# hmc830_basic.net
KiCad netlist of a schematic drawn in Altium Designer
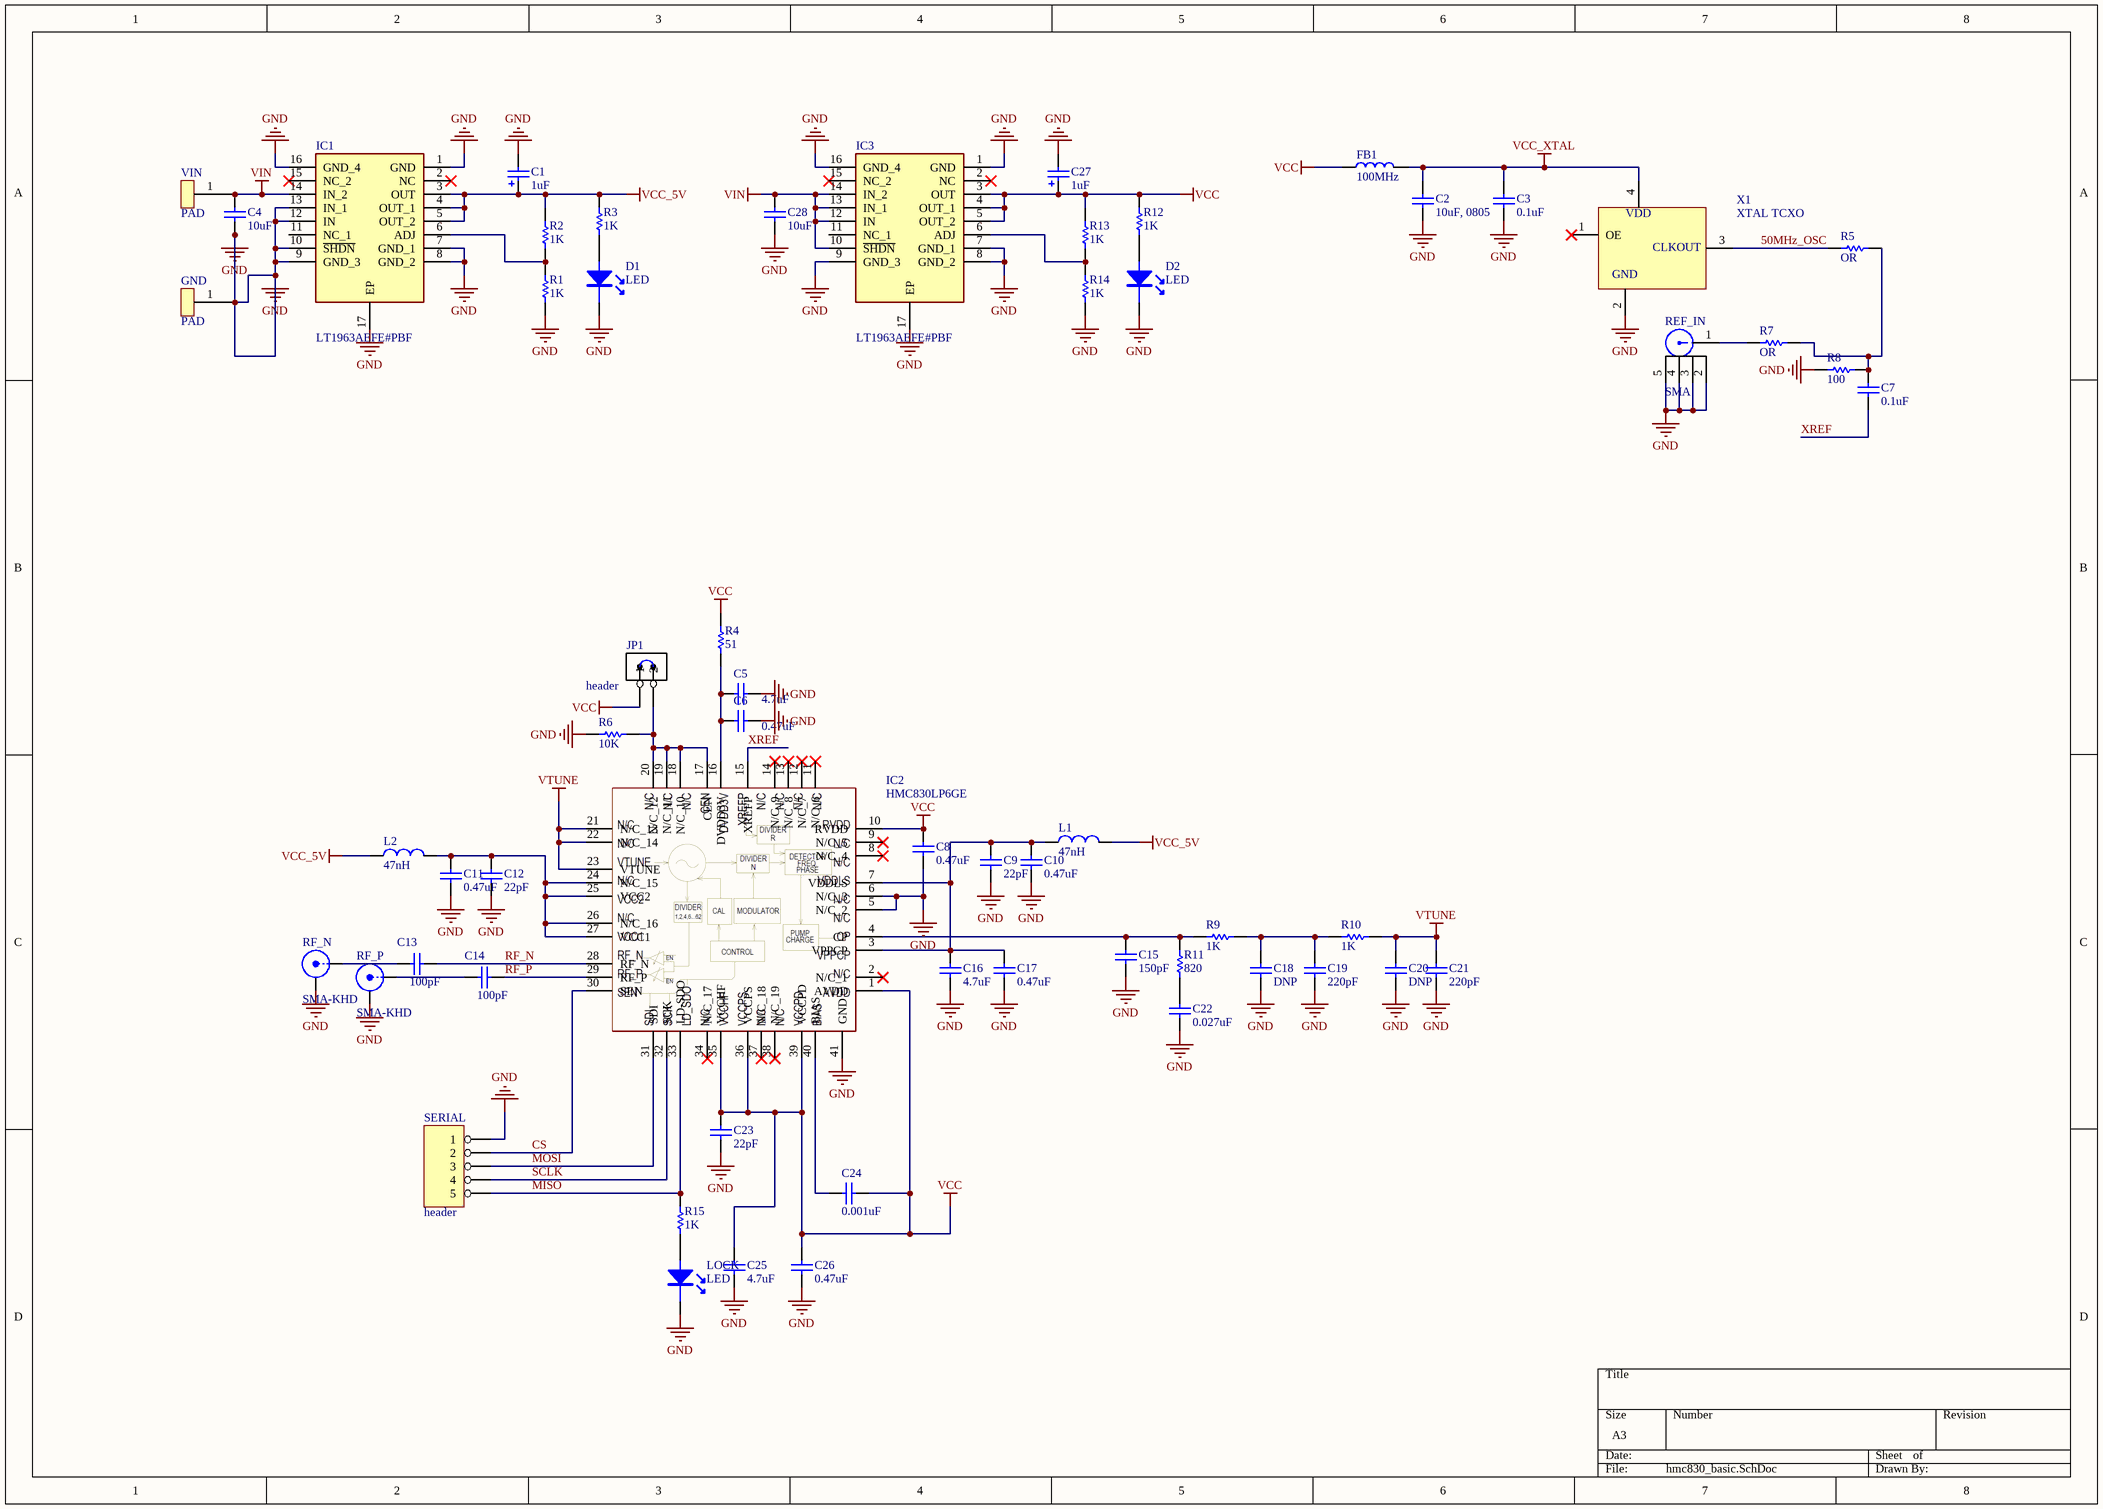
[diagram p0: hmc830_basic.SchDoc]

(export (version "E")
  (design (tool "Eeschema 10.0.6"))
  (components
    (comp (ref "C1")
      (value "1uF")
      (footprint "CAPC3528B")
      (description "Capacitor")
      (fields (field (name "PUBLISHER") "Altium Limited"))
      (libsource (lib "My Footprint") (part "CAP_tan"))
    )
    (comp (ref "C2")
      (value "10uF, 0805")
      (footprint "0805_c")
      (description "Capacitor")
      (fields (field (name "PUBLISHER") "Altium Limited"))
      (libsource (lib "My Footprint") (part "CAP"))
    )
    (comp (ref "C3")
      (value "0.1uF")
      (footprint "0603_C")
      (description "Capacitor")
      (fields (field (name "PUBLISHER") "Altium Limited"))
      (libsource (lib "My Footprint") (part "CAP"))
    )
    (comp (ref "C4")
      (value "10uF")
      (footprint "0805_c")
      (description "Capacitor")
      (fields (field (name "PUBLISHER") "Altium Limited"))
      (libsource (lib "My Footprint") (part "CAP"))
    )
    (comp (ref "C5")
      (value "4.7uF")
      (footprint "0603_C")
      (description "Capacitor")
      (fields (field (name "PUBLISHER") "Altium Limited"))
      (libsource (lib "My Footprint") (part "CAP"))
    )
    (comp (ref "C6")
      (value "0.47uF")
      (footprint "0603_C")
      (description "Capacitor")
      (fields (field (name "PUBLISHER") "Altium Limited"))
      (libsource (lib "My Footprint") (part "CAP"))
    )
    (comp (ref "C7")
      (value "0.1uF")
      (footprint "0603_C")
      (description "Capacitor")
      (fields (field (name "PUBLISHER") "Altium Limited"))
      (libsource (lib "My Footprint") (part "CAP"))
    )
    (comp (ref "C8")
      (value "0.47uF")
      (footprint "0603_C")
      (description "Capacitor")
      (fields (field (name "PUBLISHER") "Altium Limited"))
      (libsource (lib "My Footprint") (part "CAP"))
    )
    (comp (ref "C9")
      (value "22pF")
      (footprint "0603_C")
      (description "Capacitor")
      (fields (field (name "PUBLISHER") "Altium Limited"))
      (libsource (lib "My Footprint") (part "CAP"))
    )
    (comp (ref "C10")
      (value "0.47uF")
      (footprint "0603_C")
      (description "Capacitor")
      (fields (field (name "PUBLISHER") "Altium Limited"))
      (libsource (lib "My Footprint") (part "CAP"))
    )
    (comp (ref "C11")
      (value "0.47uF")
      (footprint "0603_C")
      (description "Capacitor")
      (fields (field (name "PUBLISHER") "Altium Limited"))
      (libsource (lib "My Footprint") (part "CAP"))
    )
    (comp (ref "C12")
      (value "22pF")
      (footprint "0603_C")
      (description "Capacitor")
      (fields (field (name "PUBLISHER") "Altium Limited"))
      (libsource (lib "My Footprint") (part "CAP"))
    )
    (comp (ref "C13")
      (value "100pF")
      (footprint "0603_C")
      (description "Capacitor")
      (fields (field (name "PUBLISHER") "Altium Limited"))
      (libsource (lib "My Footprint") (part "CAP"))
    )
    (comp (ref "C14")
      (value "100pF")
      (footprint "0603_C")
      (description "Capacitor")
      (fields (field (name "PUBLISHER") "Altium Limited"))
      (libsource (lib "My Footprint") (part "CAP"))
    )
    (comp (ref "C15")
      (value "150pF")
      (footprint "0603_C")
      (description "Capacitor")
      (fields (field (name "PUBLISHER") "Altium Limited"))
      (libsource (lib "My Footprint") (part "CAP"))
    )
    (comp (ref "C16")
      (value "4.7uF")
      (footprint "0603_C")
      (description "Capacitor")
      (fields (field (name "PUBLISHER") "Altium Limited"))
      (libsource (lib "My Footprint") (part "CAP"))
    )
    (comp (ref "C17")
      (value "0.47uF")
      (footprint "0603_C")
      (description "Capacitor")
      (fields (field (name "PUBLISHER") "Altium Limited"))
      (libsource (lib "My Footprint") (part "CAP"))
    )
    (comp (ref "C18")
      (value "DNP")
      (footprint "0603_C")
      (description "Capacitor")
      (fields (field (name "PUBLISHER") "Altium Limited"))
      (libsource (lib "My Footprint") (part "CAP"))
    )
    (comp (ref "C19")
      (value "220pF")
      (footprint "0603_C")
      (description "Capacitor")
      (fields (field (name "PUBLISHER") "Altium Limited"))
      (libsource (lib "My Footprint") (part "CAP"))
    )
    (comp (ref "C20")
      (value "DNP")
      (footprint "0603_C")
      (description "Capacitor")
      (fields (field (name "PUBLISHER") "Altium Limited"))
      (libsource (lib "My Footprint") (part "CAP"))
    )
    (comp (ref "C21")
      (value "220pF")
      (footprint "0603_C")
      (description "Capacitor")
      (fields (field (name "PUBLISHER") "Altium Limited"))
      (libsource (lib "My Footprint") (part "CAP"))
    )
    (comp (ref "C22")
      (value "0.027uF")
      (footprint "0603_C")
      (description "Capacitor")
      (fields (field (name "PUBLISHER") "Altium Limited"))
      (libsource (lib "My Footprint") (part "CAP"))
    )
    (comp (ref "C23")
      (value "22pF")
      (footprint "0603_C")
      (description "Capacitor")
      (fields (field (name "PUBLISHER") "Altium Limited"))
      (libsource (lib "My Footprint") (part "CAP"))
    )
    (comp (ref "C24")
      (value "0.001uF")
      (footprint "0603_C")
      (description "Capacitor")
      (fields (field (name "PUBLISHER") "Altium Limited"))
      (libsource (lib "My Footprint") (part "CAP"))
    )
    (comp (ref "C25")
      (value "4.7uF")
      (footprint "0603_C")
      (description "Capacitor")
      (fields (field (name "PUBLISHER") "Altium Limited"))
      (libsource (lib "My Footprint") (part "CAP"))
    )
    (comp (ref "C26")
      (value "0.47uF")
      (footprint "0603_C")
      (description "Capacitor")
      (fields (field (name "PUBLISHER") "Altium Limited"))
      (libsource (lib "My Footprint") (part "CAP"))
    )
    (comp (ref "C27")
      (value "1uF")
      (footprint "CAPC3528B")
      (description "Capacitor")
      (fields (field (name "PUBLISHER") "Altium Limited"))
      (libsource (lib "My Footprint") (part "CAP_tan"))
    )
    (comp (ref "C28")
      (value "10uF")
      (footprint "0805_c")
      (description "Capacitor")
      (fields (field (name "PUBLISHER") "Altium Limited"))
      (libsource (lib "My Footprint") (part "CAP"))
    )
    (comp (ref "D1")
      (value "LED")
      (footprint "0603_LED")
      (description "LED 发光二极管")
      (libsource (lib "My Footprint") (part "LED"))
    )
    (comp (ref "D2")
      (value "LED")
      (footprint "0603_LED")
      (description "LED 发光二极管")
      (libsource (lib "My Footprint") (part "LED"))
    )
    (comp (ref "FB1")
      (value "100MHz")
      (footprint "FB0603")
      (description "磁珠")
      (libsource (lib "My Footprint") (part "FB"))
    )
    (comp (ref "GND") (value "PAD") (footprint "PAD") (libsource (lib "My Footprint") (part "PAD")))
    (comp (ref "IC1")
      (value "LT1963AEFE#PBF")
      (footprint "SamacSys:SOP65P640X110-17N")
      (description "Integrated Circuit")
      (fields (field (name "MOUSER PART NUMBER") "584-LT1963AEFE#PBF"))
      (libsource (lib "SamacSys") (part "LT1963AEFE#PBF"))
    )
    (comp (ref "IC2")
      (value "HMC830LP6GE")
      (footprint "QFN50P600X600X90-41N-D")
      (description "Integrated Circuit")
      (fields
        (field (name "MOUSER PART NUMBER") "584-HMC830LP6GE")
        (field (name "RS PART NUMBER") "8626458P")
      )
      (libsource (lib "SamacSys") (part "HMC830LP6GE"))
    )
    (comp (ref "IC3")
      (value "LT1963AEFE#PBF")
      (footprint "SamacSys:SOP65P640X110-17N")
      (description "Integrated Circuit")
      (fields (field (name "MOUSER PART NUMBER") "584-LT1963AEFE#PBF"))
      (libsource (lib "SamacSys") (part "LT1963AEFE#PBF"))
    )
    (comp (ref "JP1")
      (value "header")
      (footprint "jumper")
      (libsource (lib "My Footprint") (part "HEADER 2"))
    )
    (comp (ref "L1") (value "47nH") (footprint "0603") (libsource (lib "") (part "Inductor_1")))
    (comp (ref "L2") (value "47nH") (footprint "0603") (libsource (lib "My Footprint") (part "Inductor")))
    (comp (ref "LOCK")
      (value "LED")
      (footprint "0603_LED")
      (description "LED 发光二极管")
      (libsource (lib "My Footprint") (part "LED"))
    )
    (comp (ref "R1")
      (value "1K")
      (footprint "0603_R")
      (description "Resistor")
      (fields (field (name "PUBLISHER") "Altium Limited"))
      (libsource (lib "My Footprint") (part "RES0"))
    )
    (comp (ref "R2")
      (value "1K")
      (footprint "0603_R")
      (description "Resistor")
      (fields (field (name "PUBLISHER") "Altium Limited"))
      (libsource (lib "My Footprint") (part "RES0"))
    )
    (comp (ref "R3")
      (value "1K")
      (footprint "0603_R")
      (description "Resistor")
      (fields (field (name "PUBLISHER") "Altium Limited"))
      (libsource (lib "My Footprint") (part "RES0"))
    )
    (comp (ref "R4")
      (value "51")
      (footprint "0603_R")
      (description "Resistor")
      (fields (field (name "PUBLISHER") "Altium Limited"))
      (libsource (lib "My Footprint") (part "RES0"))
    )
    (comp (ref "R5")
      (value "OR")
      (footprint "0603_R")
      (description "Resistor")
      (fields (field (name "PUBLISHER") "Altium Limited"))
      (libsource (lib "My Footprint") (part "RES0"))
    )
    (comp (ref "R6")
      (value "10K")
      (footprint "0603_R")
      (description "Resistor")
      (fields (field (name "PUBLISHER") "Altium Limited"))
      (libsource (lib "My Footprint") (part "RES0"))
    )
    (comp (ref "R7")
      (value "OR")
      (footprint "0603_R")
      (description "Resistor")
      (fields (field (name "PUBLISHER") "Altium Limited"))
      (libsource (lib "My Footprint") (part "RES0"))
    )
    (comp (ref "R8")
      (value "100")
      (footprint "0603_R")
      (description "Resistor")
      (fields (field (name "PUBLISHER") "Altium Limited"))
      (libsource (lib "My Footprint") (part "RES0"))
    )
    (comp (ref "R9")
      (value "1K")
      (footprint "0603_R")
      (description "Resistor")
      (fields (field (name "PUBLISHER") "Altium Limited"))
      (libsource (lib "My Footprint") (part "RES0"))
    )
    (comp (ref "R10")
      (value "1K")
      (footprint "0603_R")
      (description "Resistor")
      (fields (field (name "PUBLISHER") "Altium Limited"))
      (libsource (lib "My Footprint") (part "RES0"))
    )
    (comp (ref "R11")
      (value "820")
      (footprint "0603_R")
      (description "Resistor")
      (fields (field (name "PUBLISHER") "Altium Limited"))
      (libsource (lib "My Footprint") (part "RES0"))
    )
    (comp (ref "R12")
      (value "1K")
      (footprint "0603_R")
      (description "Resistor")
      (fields (field (name "PUBLISHER") "Altium Limited"))
      (libsource (lib "My Footprint") (part "RES0"))
    )
    (comp (ref "R13")
      (value "1K")
      (footprint "0603_R")
      (description "Resistor")
      (fields (field (name "PUBLISHER") "Altium Limited"))
      (libsource (lib "My Footprint") (part "RES0"))
    )
    (comp (ref "R14")
      (value "1K")
      (footprint "0603_R")
      (description "Resistor")
      (fields (field (name "PUBLISHER") "Altium Limited"))
      (libsource (lib "My Footprint") (part "RES0"))
    )
    (comp (ref "R15")
      (value "1K")
      (footprint "0603_R")
      (description "Resistor")
      (fields (field (name "PUBLISHER") "Altium Limited"))
      (libsource (lib "My Footprint") (part "RES0"))
    )
    (comp (ref "REF_IN") (value "SMA") (footprint "SMA-KE") (libsource (lib "My Footprint") (part "SMA")))
    (comp (ref "RF_N")
      (value "SMA-KHD")
      (footprint "SMA-2")
      (libsource (lib "My Footprint") (part "SMA_KHD"))
    )
    (comp (ref "RF_P")
      (value "SMA-KHD")
      (footprint "SMA-2")
      (libsource (lib "My Footprint") (part "SMA_KHD"))
    )
    (comp (ref "SERIAL")
      (value "header")
      (footprint "header5")
      (libsource (lib "My Footprint") (part "HEADER 5"))
    )
    (comp (ref "VIN") (value "PAD") (footprint "PAD") (libsource (lib "My Footprint") (part "PAD")))
    (comp (ref "X1")
      (value "XTAL TCXO")
      (footprint "OSC_KH3225_4P")
      (libsource (lib "My Footprint") (part "xtal_tcxo"))
    )
  )
  (nets
    (net (code "1") (name "/50MHz_OSC") (class "Default")
      (node (ref "R5") (pin "2") (pinfunction "2_2") (pintype "passive"))
      (node (ref "X1") (pin "3") (pinfunction "CLK_OUT_3") (pintype "passive"))
    )
    (net (code "2") (name "/CS") (class "Default")
      (node (ref "IC2") (pin "30") (pinfunction "SEN_30") (pintype "passive"))
      (node (ref "SERIAL") (pin "2") (pinfunction "2_2") (pintype "passive"))
    )
    (net (code "3") (name "/MISO") (class "Default")
      (node (ref "IC2") (pin "33") (pinfunction "LD-SDO_33") (pintype "passive"))
      (node (ref "R15") (pin "2") (pinfunction "2_2") (pintype "passive"))
      (node (ref "SERIAL") (pin "5") (pinfunction "5_5") (pintype "passive"))
    )
    (net (code "4") (name "/MOSI") (class "Default")
      (node (ref "IC2") (pin "31") (pinfunction "SDI_31") (pintype "passive"))
      (node (ref "SERIAL") (pin "3") (pinfunction "3_3") (pintype "passive"))
    )
    (net (code "5") (name "/RF_N") (class "Default")
      (node (ref "C13") (pin "2") (pinfunction "2_2") (pintype "passive"))
      (node (ref "IC2") (pin "28") (pinfunction "RF_N_28") (pintype "passive"))
    )
    (net (code "6") (name "/RF_P") (class "Default")
      (node (ref "C14") (pin "2") (pinfunction "2_2") (pintype "passive"))
      (node (ref "IC2") (pin "29") (pinfunction "RF_P_29") (pintype "passive"))
    )
    (net (code "7") (name "/SCLK") (class "Default")
      (node (ref "IC2") (pin "32") (pinfunction "SCK_32") (pintype "passive"))
      (node (ref "SERIAL") (pin "4") (pinfunction "4_4") (pintype "passive"))
    )
    (net (code "8") (name "/XREF") (class "Default")
      (node (ref "C7") (pin "1") (pinfunction "1_1") (pintype "passive"))
      (node (ref "IC2") (pin "15") (pinfunction "XREFP_15") (pintype "passive"))
    )
    (net (code "9") (name "GND") (class "Default")
      (node (ref "C1") (pin "2") (pinfunction "2_2") (pintype "passive"))
      (node (ref "C10") (pin "1") (pinfunction "1_1") (pintype "passive"))
      (node (ref "C11") (pin "1") (pinfunction "1_1") (pintype "passive"))
      (node (ref "C12") (pin "1") (pinfunction "1_1") (pintype "passive"))
      (node (ref "C15") (pin "1") (pinfunction "1_1") (pintype "passive"))
      (node (ref "C16") (pin "1") (pinfunction "1_1") (pintype "passive"))
      (node (ref "C17") (pin "1") (pinfunction "1_1") (pintype "passive"))
      (node (ref "C18") (pin "1") (pinfunction "1_1") (pintype "passive"))
      (node (ref "C19") (pin "1") (pinfunction "1_1") (pintype "passive"))
      (node (ref "C2") (pin "1") (pinfunction "1_1") (pintype "passive"))
      (node (ref "C20") (pin "1") (pinfunction "1_1") (pintype "passive"))
      (node (ref "C21") (pin "1") (pinfunction "1_1") (pintype "passive"))
      (node (ref "C22") (pin "1") (pinfunction "1_1") (pintype "passive"))
      (node (ref "C23") (pin "1") (pinfunction "1_1") (pintype "passive"))
      (node (ref "C25") (pin "1") (pinfunction "1_1") (pintype "passive"))
      (node (ref "C26") (pin "1") (pinfunction "1_1") (pintype "passive"))
      (node (ref "C27") (pin "2") (pinfunction "2_2") (pintype "passive"))
      (node (ref "C28") (pin "1") (pinfunction "1_1") (pintype "passive"))
      (node (ref "C3") (pin "1") (pinfunction "1_1") (pintype "passive"))
      (node (ref "C4") (pin "1") (pinfunction "1_1") (pintype "passive"))
      (node (ref "C5") (pin "2") (pinfunction "2_2") (pintype "passive"))
      (node (ref "C6") (pin "2") (pinfunction "2_2") (pintype "passive"))
      (node (ref "C8") (pin "1") (pinfunction "1_1") (pintype "passive"))
      (node (ref "C9") (pin "1") (pinfunction "1_1") (pintype "passive"))
      (node (ref "D1") (pin "2") (pinfunction "K_2") (pintype "passive"))
      (node (ref "D2") (pin "2") (pinfunction "K_2") (pintype "passive"))
      (node (ref "GND") (pin "1") (pintype "passive"))
      (node (ref "IC1") (pin "1") (pinfunction "GND_1") (pintype "power_in"))
      (node (ref "IC1") (pin "10") (pinfunction "~{SHDN}_10") (pintype "passive"))
      (node (ref "IC1") (pin "12") (pinfunction "IN_12") (pintype "passive"))
      (node (ref "IC1") (pin "13") (pinfunction "IN_1_13") (pintype "passive"))
      (node (ref "IC1") (pin "16") (pinfunction "GND_4_16") (pintype "power_in"))
      (node (ref "IC1") (pin "17") (pinfunction "EP_17") (pintype "power_in"))
      (node (ref "IC1") (pin "7") (pinfunction "GND_1_7") (pintype "power_in"))
      (node (ref "IC1") (pin "8") (pinfunction "GND_2_8") (pintype "power_in"))
      (node (ref "IC1") (pin "9") (pinfunction "GND_3_9") (pintype "power_in"))
      (node (ref "IC2") (pin "41") (pinfunction "GND_41") (pintype "passive"))
      (node (ref "IC2") (pin "5") (pinfunction "N/C_2_5") (pintype "passive"))
      (node (ref "IC2") (pin "6") (pinfunction "N/C_3_6") (pintype "passive"))
      (node (ref "IC3") (pin "1") (pinfunction "GND_1") (pintype "power_in"))
      (node (ref "IC3") (pin "16") (pinfunction "GND_4_16") (pintype "power_in"))
      (node (ref "IC3") (pin "17") (pinfunction "EP_17") (pintype "power_in"))
      (node (ref "IC3") (pin "7") (pinfunction "GND_1_7") (pintype "power_in"))
      (node (ref "IC3") (pin "8") (pinfunction "GND_2_8") (pintype "power_in"))
      (node (ref "IC3") (pin "9") (pinfunction "GND_3_9") (pintype "power_in"))
      (node (ref "LOCK") (pin "2") (pinfunction "K_2") (pintype "passive"))
      (node (ref "R1") (pin "1") (pinfunction "1_1") (pintype "passive"))
      (node (ref "R14") (pin "1") (pinfunction "1_1") (pintype "passive"))
      (node (ref "R6") (pin "1") (pinfunction "1_1") (pintype "passive"))
      (node (ref "R8") (pin "2") (pinfunction "2_2") (pintype "passive"))
      (node (ref "REF_IN") (pin "2") (pinfunction "GND_2") (pintype "passive"))
      (node (ref "REF_IN") (pin "3") (pinfunction "GND_3") (pintype "passive"))
      (node (ref "REF_IN") (pin "4") (pinfunction "GND_4") (pintype "passive"))
      (node (ref "REF_IN") (pin "5") (pinfunction "GND_5") (pintype "passive"))
      (node (ref "RF_N") (pin "1") (pinfunction "Y_1") (pintype "passive"))
      (node (ref "RF_P") (pin "1") (pinfunction "Y_1") (pintype "passive"))
      (node (ref "SERIAL") (pin "1") (pinfunction "1_1") (pintype "passive"))
      (node (ref "X1") (pin "2") (pinfunction "GND_2") (pintype "passive"))
    )
    (net (code "10") (name "Net-(C7-Pad2)") (class "Default")
      (node (ref "C7") (pin "2") (pinfunction "2_2") (pintype "passive"))
      (node (ref "R5") (pin "1") (pinfunction "1_1") (pintype "passive"))
      (node (ref "R7") (pin "1") (pinfunction "1_1") (pintype "passive"))
      (node (ref "R8") (pin "1") (pinfunction "1_1") (pintype "passive"))
    )
    (net (code "11") (name "Net-(C18-Pad2)") (class "Default")
      (node (ref "C18") (pin "2") (pinfunction "2_2") (pintype "passive"))
      (node (ref "C19") (pin "2") (pinfunction "2_2") (pintype "passive"))
      (node (ref "R10") (pin "1") (pinfunction "1_1") (pintype "passive"))
      (node (ref "R9") (pin "2") (pinfunction "2_2") (pintype "passive"))
    )
    (net (code "12") (name "Net-(C22-Pad2)") (class "Default")
      (node (ref "C22") (pin "2") (pinfunction "2_2") (pintype "passive"))
      (node (ref "R11") (pin "1") (pinfunction "1_1") (pintype "passive"))
    )
    (net (code "13") (name "Net-(D1-A)") (class "Default")
      (node (ref "D1") (pin "1") (pinfunction "A_1") (pintype "passive"))
      (node (ref "R3") (pin "1") (pinfunction "1_1") (pintype "passive"))
    )
    (net (code "14") (name "Net-(D2-A)") (class "Default")
      (node (ref "D2") (pin "1") (pinfunction "A_1") (pintype "passive"))
      (node (ref "R12") (pin "1") (pinfunction "1_1") (pintype "passive"))
    )
    (net (code "15") (name "Net-(IC1-ADJ)") (class "Default")
      (node (ref "IC1") (pin "6") (pinfunction "ADJ_6") (pintype "passive"))
      (node (ref "R1") (pin "2") (pinfunction "2_2") (pintype "passive"))
      (node (ref "R2") (pin "1") (pinfunction "1_1") (pintype "passive"))
    )
    (net (code "16") (name "Net-(IC2-BIAS)") (class "Default")
      (node (ref "C24") (pin "2") (pinfunction "2_2") (pintype "passive"))
      (node (ref "IC2") (pin "40") (pinfunction "BIAS_40") (pintype "passive"))
    )
    (net (code "17") (name "Net-(IC2-CEN)") (class "Default")
      (node (ref "IC2") (pin "17") (pinfunction "CEN_17") (pintype "passive"))
      (node (ref "IC2") (pin "18") (pinfunction "N/C_10_18") (pintype "passive"))
      (node (ref "IC2") (pin "19") (pinfunction "N/C_11_19") (pintype "passive"))
      (node (ref "IC2") (pin "20") (pinfunction "N/C_12_20") (pintype "passive"))
      (node (ref "JP1") (pin "2") (pinfunction "2_2") (pintype "passive"))
      (node (ref "R6") (pin "2") (pinfunction "2_2") (pintype "passive"))
    )
    (net (code "18") (name "Net-(IC2-CP)") (class "Default")
      (node (ref "C15") (pin "2") (pinfunction "2_2") (pintype "passive"))
      (node (ref "IC2") (pin "4") (pinfunction "CP_4") (pintype "passive"))
      (node (ref "R11") (pin "2") (pinfunction "2_2") (pintype "passive"))
      (node (ref "R9") (pin "1") (pinfunction "1_1") (pintype "passive"))
    )
    (net (code "19") (name "Net-(IC2-DVDD3V)") (class "Default")
      (node (ref "C5") (pin "1") (pinfunction "1_1") (pintype "passive"))
      (node (ref "C6") (pin "1") (pinfunction "1_1") (pintype "passive"))
      (node (ref "IC2") (pin "16") (pinfunction "DVDD3V_16") (pintype "passive"))
      (node (ref "R4") (pin "1") (pinfunction "1_1") (pintype "passive"))
    )
    (net (code "20") (name "Net-(IC2-N{slash}C_15)") (class "Default")
      (node (ref "C11") (pin "2") (pinfunction "2_2") (pintype "passive"))
      (node (ref "C12") (pin "2") (pinfunction "2_2") (pintype "passive"))
      (node (ref "IC2") (pin "24") (pinfunction "N/C_15_24") (pintype "passive"))
      (node (ref "IC2") (pin "25") (pinfunction "VCC2_25") (pintype "passive"))
      (node (ref "IC2") (pin "26") (pinfunction "N/C_16_26") (pintype "passive"))
      (node (ref "IC2") (pin "27") (pinfunction "VCC1_27") (pintype "passive"))
      (node (ref "L2") (pin "2") (pinfunction "2_2") (pintype "passive"))
    )
    (net (code "21") (name "Net-(IC2-VDDLS)") (class "Default")
      (node (ref "C10") (pin "2") (pinfunction "2_2") (pintype "passive"))
      (node (ref "C16") (pin "2") (pinfunction "2_2") (pintype "passive"))
      (node (ref "C17") (pin "2") (pinfunction "2_2") (pintype "passive"))
      (node (ref "C9") (pin "2") (pinfunction "2_2") (pintype "passive"))
      (node (ref "IC2") (pin "3") (pinfunction "VPPCP_3") (pintype "passive"))
      (node (ref "IC2") (pin "7") (pinfunction "VDDLS_7") (pintype "passive"))
      (node (ref "L1") (pin "2") (pinfunction "2_2") (pintype "passive"))
    )
    (net (code "22") (name "Net-(IC3-ADJ)") (class "Default")
      (node (ref "IC3") (pin "6") (pinfunction "ADJ_6") (pintype "passive"))
      (node (ref "R13") (pin "1") (pinfunction "1_1") (pintype "passive"))
      (node (ref "R14") (pin "2") (pinfunction "2_2") (pintype "passive"))
    )
    (net (code "23") (name "Net-(LOCK-A)") (class "Default")
      (node (ref "LOCK") (pin "1") (pinfunction "A_1") (pintype "passive"))
      (node (ref "R15") (pin "1") (pinfunction "1_1") (pintype "passive"))
    )
    (net (code "24") (name "Net-(REF_IN-vcc)") (class "Default")
      (node (ref "R7") (pin "2") (pinfunction "2_2") (pintype "passive"))
      (node (ref "REF_IN") (pin "1") (pinfunction "vcc_1") (pintype "passive"))
    )
    (net (code "25") (name "Net-(RF_N-X)") (class "Default")
      (node (ref "C13") (pin "1") (pinfunction "1_1") (pintype "passive"))
      (node (ref "RF_N") (pin "2") (pinfunction "X_2") (pintype "passive"))
    )
    (net (code "26") (name "Net-(RF_P-X)") (class "Default")
      (node (ref "C14") (pin "1") (pinfunction "1_1") (pintype "passive"))
      (node (ref "RF_P") (pin "2") (pinfunction "X_2") (pintype "passive"))
    )
    (net (code "27") (name "VCC") (class "Default")
      (node (ref "C23") (pin "2") (pinfunction "2_2") (pintype "passive"))
      (node (ref "C24") (pin "1") (pinfunction "1_1") (pintype "passive"))
      (node (ref "C25") (pin "2") (pinfunction "2_2") (pintype "passive"))
      (node (ref "C26") (pin "2") (pinfunction "2_2") (pintype "passive"))
      (node (ref "C27") (pin "1") (pinfunction "1_1") (pintype "passive"))
      (node (ref "C8") (pin "2") (pinfunction "2_2") (pintype "passive"))
      (node (ref "FB1") (pin "1") (pinfunction "1_1") (pintype "passive"))
      (node (ref "IC2") (pin "1") (pinfunction "AVDD_1") (pintype "passive"))
      (node (ref "IC2") (pin "10") (pinfunction "RVDD_10") (pintype "passive"))
      (node (ref "IC2") (pin "35") (pinfunction "VCCHF_35") (pintype "passive"))
      (node (ref "IC2") (pin "36") (pinfunction "VCCPS_36") (pintype "passive"))
      (node (ref "IC2") (pin "39") (pinfunction "VCCPD_39") (pintype "passive"))
      (node (ref "IC3") (pin "3") (pinfunction "OUT_3") (pintype "passive"))
      (node (ref "IC3") (pin "4") (pinfunction "OUT_1_4") (pintype "passive"))
      (node (ref "IC3") (pin "5") (pinfunction "OUT_2_5") (pintype "passive"))
      (node (ref "JP1") (pin "1") (pinfunction "1_1") (pintype "passive"))
      (node (ref "R12") (pin "2") (pinfunction "2_2") (pintype "passive"))
      (node (ref "R13") (pin "2") (pinfunction "2_2") (pintype "passive"))
      (node (ref "R4") (pin "2") (pinfunction "2_2") (pintype "passive"))
    )
    (net (code "28") (name "VCC_5V") (class "Default")
      (node (ref "C1") (pin "1") (pinfunction "1_1") (pintype "passive"))
      (node (ref "IC1") (pin "3") (pinfunction "OUT_3") (pintype "passive"))
      (node (ref "IC1") (pin "4") (pinfunction "OUT_1_4") (pintype "passive"))
      (node (ref "IC1") (pin "5") (pinfunction "OUT_2_5") (pintype "passive"))
      (node (ref "L1") (pin "1") (pinfunction "1_1") (pintype "passive"))
      (node (ref "L2") (pin "1") (pinfunction "1_1") (pintype "passive"))
      (node (ref "R2") (pin "2") (pinfunction "2_2") (pintype "passive"))
      (node (ref "R3") (pin "2") (pinfunction "2_2") (pintype "passive"))
    )
    (net (code "29") (name "VCC_XTAL") (class "Default")
      (node (ref "C2") (pin "2") (pinfunction "2_2") (pintype "passive"))
      (node (ref "C3") (pin "2") (pinfunction "2_2") (pintype "passive"))
      (node (ref "FB1") (pin "2") (pinfunction "2_2") (pintype "passive"))
      (node (ref "X1") (pin "4") (pinfunction "VDD_4") (pintype "passive"))
    )
    (net (code "30") (name "VIN") (class "Default")
      (node (ref "C28") (pin "2") (pinfunction "2_2") (pintype "passive"))
      (node (ref "C4") (pin "2") (pinfunction "2_2") (pintype "passive"))
      (node (ref "IC1") (pin "14") (pinfunction "IN_2_14") (pintype "passive"))
      (node (ref "IC3") (pin "10") (pinfunction "~{SHDN}_10") (pintype "passive"))
      (node (ref "IC3") (pin "12") (pinfunction "IN_12") (pintype "passive"))
      (node (ref "IC3") (pin "13") (pinfunction "IN_1_13") (pintype "passive"))
      (node (ref "IC3") (pin "14") (pinfunction "IN_2_14") (pintype "passive"))
      (node (ref "VIN") (pin "1") (pintype "passive"))
    )
    (net (code "31") (name "VTUNE") (class "Default")
      (node (ref "C20") (pin "2") (pinfunction "2_2") (pintype "passive"))
      (node (ref "C21") (pin "2") (pinfunction "2_2") (pintype "passive"))
      (node (ref "IC2") (pin "21") (pinfunction "N/C_13_21") (pintype "passive"))
      (node (ref "IC2") (pin "22") (pinfunction "N/C_14_22") (pintype "passive"))
      (node (ref "IC2") (pin "23") (pinfunction "VTUNE_23") (pintype "passive"))
      (node (ref "R10") (pin "2") (pinfunction "2_2") (pintype "passive"))
    )
    (net (code "32") (name "unconnected-(IC1-NC-Pad2)") (class "Default")
      (node (ref "IC1") (pin "2") (pinfunction "NC_2") (pintype "passive+no_connect"))
    )
    (net (code "33") (name "unconnected-(IC1-NC_1-Pad11)") (class "Default")
      (node (ref "IC1") (pin "11") (pinfunction "NC_1_11") (pintype "passive"))
    )
    (net (code "34") (name "unconnected-(IC1-NC_2-Pad15)") (class "Default")
      (node (ref "IC1") (pin "15") (pinfunction "NC_2_15") (pintype "passive+no_connect"))
    )
    (net (code "35") (name "unconnected-(IC2-N{slash}C_1-Pad2)") (class "Default")
      (node (ref "IC2") (pin "2") (pinfunction "N/C_1_2") (pintype "passive+no_connect"))
    )
    (net (code "36") (name "unconnected-(IC2-N{slash}C_4-Pad8)") (class "Default")
      (node (ref "IC2") (pin "8") (pinfunction "N/C_4_8") (pintype "passive+no_connect"))
    )
    (net (code "37") (name "unconnected-(IC2-N{slash}C_5-Pad9)") (class "Default")
      (node (ref "IC2") (pin "9") (pinfunction "N/C_5_9") (pintype "passive+no_connect"))
    )
    (net (code "38") (name "unconnected-(IC2-N{slash}C_6-Pad11)") (class "Default")
      (node (ref "IC2") (pin "11") (pinfunction "N/C_6_11") (pintype "passive+no_connect"))
    )
    (net (code "39") (name "unconnected-(IC2-N{slash}C_7-Pad12)") (class "Default")
      (node (ref "IC2") (pin "12") (pinfunction "N/C_7_12") (pintype "passive+no_connect"))
    )
    (net (code "40") (name "unconnected-(IC2-N{slash}C_8-Pad13)") (class "Default")
      (node (ref "IC2") (pin "13") (pinfunction "N/C_8_13") (pintype "passive+no_connect"))
    )
    (net (code "41") (name "unconnected-(IC2-N{slash}C_9-Pad14)") (class "Default")
      (node (ref "IC2") (pin "14") (pinfunction "N/C_9_14") (pintype "passive+no_connect"))
    )
    (net (code "42") (name "unconnected-(IC2-N{slash}C_17-Pad34)") (class "Default")
      (node (ref "IC2") (pin "34") (pinfunction "N/C_17_34") (pintype "passive+no_connect"))
    )
    (net (code "43") (name "unconnected-(IC2-N{slash}C_18-Pad37)") (class "Default")
      (node (ref "IC2") (pin "37") (pinfunction "N/C_18_37") (pintype "passive+no_connect"))
    )
    (net (code "44") (name "unconnected-(IC2-N{slash}C_19-Pad38)") (class "Default")
      (node (ref "IC2") (pin "38") (pinfunction "N/C_19_38") (pintype "passive+no_connect"))
    )
    (net (code "45") (name "unconnected-(IC3-NC-Pad2)") (class "Default")
      (node (ref "IC3") (pin "2") (pinfunction "NC_2") (pintype "passive+no_connect"))
    )
    (net (code "46") (name "unconnected-(IC3-NC_1-Pad11)") (class "Default")
      (node (ref "IC3") (pin "11") (pinfunction "NC_1_11") (pintype "passive"))
    )
    (net (code "47") (name "unconnected-(IC3-NC_2-Pad15)") (class "Default")
      (node (ref "IC3") (pin "15") (pinfunction "NC_2_15") (pintype "passive+no_connect"))
    )
    (net (code "48") (name "unconnected-(X1-OE-Pad1)") (class "Default")
      (node (ref "X1") (pin "1") (pinfunction "OE_1") (pintype "passive+no_connect"))
    )
  )
)
